# EEPROM.net
KiCad netlist of a schematic drawn in Altium Designer
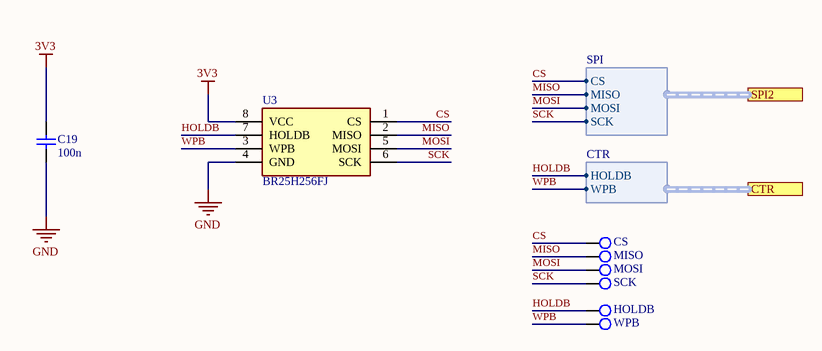
[diagram p0: EEPROM.SchDoc]

(export (version "E")
  (design (tool "Eeschema 10.0.6"))
  (components
    (comp (ref "C19")
      (value "100n")
      (footprint "Cap_0603_MD_outline")
      (description "Capacitor")
      (fields (field (name "MPN") "GRM188R72A104KA35"))
      (libsource (lib "LibPassive") (part "Capacitor"))
    )
    (comp (ref "TP10")
      (value "CS")
      (footprint "TP_SQ25x40")
      (description "Test point")
      (libsource (lib "Library") (part "TestPoint"))
    )
    (comp (ref "TP11")
      (value "MISO")
      (footprint "TP_SQ25x40")
      (description "Test point")
      (libsource (lib "Library") (part "TestPoint"))
    )
    (comp (ref "TP12")
      (value "MOSI")
      (footprint "TP_SQ25x40")
      (description "Test point")
      (libsource (lib "Library") (part "TestPoint"))
    )
    (comp (ref "TP13")
      (value "SCK")
      (footprint "TP_SQ25x40")
      (description "Test point")
      (libsource (lib "Library") (part "TestPoint"))
    )
    (comp (ref "TP14")
      (value "HOLDB")
      (footprint "TP_SQ25x40")
      (description "Test point")
      (libsource (lib "Library") (part "TestPoint"))
    )
    (comp (ref "TP15")
      (value "WPB")
      (footprint "TP_SQ25x40")
      (description "Test point")
      (libsource (lib "Library") (part "TestPoint"))
    )
    (comp (ref "U3")
      (value "BR25H256FJ")
      (footprint "SOIC127P600X165-8N")
      (description "EEPROM")
      (fields
        (field (name "MOUSER PART NUMBER") "755-BR25H256FJ-2ACE2")
        (field (name "MPN") "BR25H256FJ-2ACE2")
      )
      (libsource (lib "Library") (part "BR25H256FJ"))
    )
  )
  (nets
    (net (code "3") (name "/CS") (class "Default")
      (node (ref "TP10") (pin "1") (pintype "passive"))
      (node (ref "U3") (pin "1") (pinfunction "CS_1") (pintype "passive"))
    )
    (net (code "4") (name "/HOLDB") (class "Default")
      (node (ref "TP14") (pin "1") (pintype "passive"))
      (node (ref "U3") (pin "7") (pinfunction "HOLDB_7") (pintype "passive"))
    )
    (net (code "5") (name "/MISO") (class "Default")
      (node (ref "TP11") (pin "1") (pintype "passive"))
      (node (ref "U3") (pin "2") (pinfunction "MISO_2") (pintype "passive"))
    )
    (net (code "6") (name "/MOSI") (class "Default")
      (node (ref "TP12") (pin "1") (pintype "passive"))
      (node (ref "U3") (pin "5") (pinfunction "MOSI_5") (pintype "passive"))
    )
    (net (code "7") (name "/SCK") (class "Default")
      (node (ref "TP13") (pin "1") (pintype "passive"))
      (node (ref "U3") (pin "6") (pinfunction "SCK_6") (pintype "passive"))
    )
    (net (code "8") (name "/WPB") (class "Default")
      (node (ref "TP15") (pin "1") (pintype "passive"))
      (node (ref "U3") (pin "3") (pinfunction "WPB_3") (pintype "passive"))
    )
    (net (code "11") (name "3V3") (class "Default")
      (node (ref "C19") (pin "2") (pinfunction "2_2") (pintype "passive"))
      (node (ref "U3") (pin "8") (pinfunction "VCC_8") (pintype "passive"))
    )
    (net (code "12") (name "GND") (class "Default")
      (node (ref "C19") (pin "1") (pinfunction "1_1") (pintype "passive"))
      (node (ref "U3") (pin "4") (pinfunction "GND_4") (pintype "passive"))
    )
  )
)
